# Alimentacion.net
KiCad netlist of a schematic drawn in Altium Designer
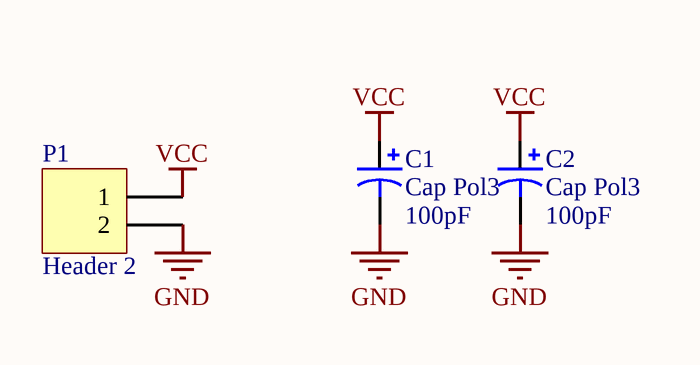
[diagram p0: Alimentacion.SchDoc]

(export (version "E")
  (design (tool "Eeschema 10.0.6"))
  (components
    (comp (ref "C1")
      (value "Cap Pol3")
      (footprint "C0805")
      (description "Polarized Capacitor (Surface Mount)")
      (fields (field (name "ALTIUM_VALUE") "100pF") (field (name "PUBLISHER") "Altium Limited"))
      (libsource (lib "Miscellaneous Devices") (part "Cap Pol3"))
    )
    (comp (ref "C2")
      (value "Cap Pol3")
      (footprint "C0805")
      (description "Polarized Capacitor (Surface Mount)")
      (fields (field (name "ALTIUM_VALUE") "100pF") (field (name "PUBLISHER") "Altium Limited"))
      (libsource (lib "Miscellaneous Devices") (part "Cap Pol3"))
    )
    (comp (ref "P1")
      (value "Header 2")
      (footprint "HDR1X2")
      (description "Header, 2-Pin")
      (fields (field (name "PUBLISHER") "Altium Limited"))
      (libsource (lib "Miscellaneous Connectors") (part "Header 2"))
    )
  )
  (nets
    (net (code "1") (name "GND") (class "Default")
      (node (ref "C1") (pin "2") (pinfunction "2_2") (pintype "passive"))
      (node (ref "C2") (pin "2") (pinfunction "2_2") (pintype "passive"))
      (node (ref "P1") (pin "2") (pinfunction "2_2") (pintype "passive"))
    )
    (net (code "2") (name "VCC") (class "Default")
      (node (ref "C1") (pin "1") (pinfunction "1_1") (pintype "passive"))
      (node (ref "C2") (pin "1") (pinfunction "1_1") (pintype "passive"))
      (node (ref "P1") (pin "1") (pinfunction "1_1") (pintype "passive"))
    )
  )
)
